# 04_MOSFET.net
KiCad netlist of a schematic drawn in Altium Designer
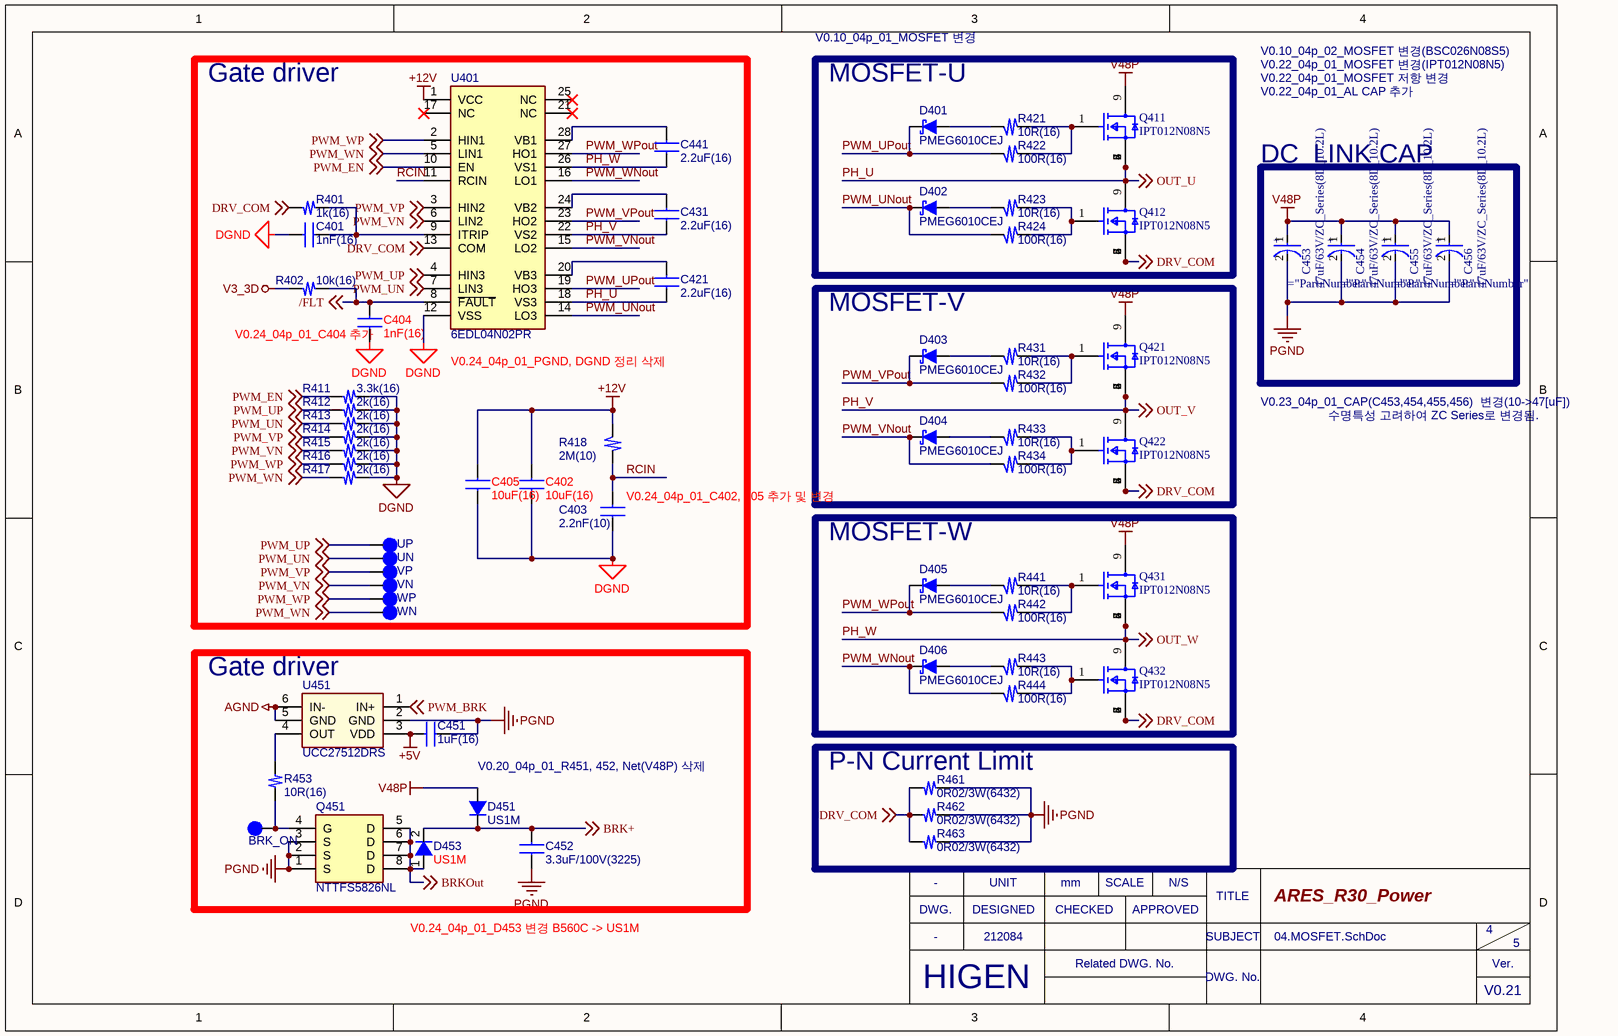
[diagram p0: 04.MOSFET.SchDoc]

(export (version "E")
  (design (tool "Eeschema 10.0.6"))
  (components
    (comp (ref "BRK_ON")
      (value "TP")
      (footprint "TP-SMD")
      (fields (field (name "MFR") "Keystone Electronics") (field (name "TIINTPARTNUMBER") "2H0026"))
      (libsource (lib "*") (part "2H_TestPointThroughHole"))
    )
    (comp (ref "C401")
      (value "1nF(16)")
      (footprint "C-1608S")
      (libsource (lib "AM437X_MAIN_LOW") (part "Cap_NP"))
    )
    (comp (ref "C402") (value "10uF(16)") (footprint "C-1608S") (libsource (lib "HIGEN") (part "Cap_NP")))
    (comp (ref "C403") (value "2.2nF(10)") (footprint "C-1005S") (libsource (lib "HIGEN") (part "Cap_NP")))
    (comp (ref "C404")
      (value "1nF(16)")
      (footprint "C-1608S")
      (libsource (lib "AM437X_MAIN_LOW") (part "Cap_NP"))
    )
    (comp (ref "C405") (value "10uF(16)") (footprint "C-1608S") (libsource (lib "HIGEN") (part "Cap_NP")))
    (comp (ref "C421") (value "2.2uF(16)") (footprint "C-1608S") (libsource (lib "HIGEN") (part "Cap_NP")))
    (comp (ref "C431") (value "2.2uF(16)") (footprint "C-1608S") (libsource (lib "HIGEN") (part "Cap_NP")))
    (comp (ref "C441") (value "2.2uF(16)") (footprint "C-1608S") (libsource (lib "HIGEN") (part "Cap_NP")))
    (comp (ref "C451")
      (value "1uF(16)")
      (footprint "C-1608S")
      (libsource (lib "AM437X_MAIN_LOW") (part "Cap_NP"))
    )
    (comp (ref "C452")
      (value "3.3uF/100V(3225)")
      (footprint "C-3225")
      (libsource (lib "HIGEN") (part "Cap_NP"))
    )
    (comp (ref "C453")
      (value "47uF/63V/ZC_Series(8D_10.2L)")
      (footprint "EC-H10")
      (description "EEE-FK1J680UP")
      (libsource (lib "ARES_R30_Power_r1") (part "EEE-FK1J680UP"))
    )
    (comp (ref "C454")
      (value "47uF/63V/ZC_Series(8D_10.2L)")
      (footprint "EC-H10")
      (description "EEE-FK1J680UP")
      (libsource (lib "ARES_R30_Power_r1") (part "EEE-FK1J680UP"))
    )
    (comp (ref "C455")
      (value "47uF/63V/ZC_Series(8D_10.2L)")
      (footprint "EC-H10")
      (description "EEE-FK1J680UP")
      (libsource (lib "ARES_R30_Power_r1") (part "EEE-FK1J680UP"))
    )
    (comp (ref "C456")
      (value "47uF/63V/ZC_Series(8D_10.2L)")
      (footprint "EC-H10")
      (description "EEE-FK1J680UP")
      (libsource (lib "ARES_R30_Power_r1") (part "EEE-FK1J680UP"))
    )
    (comp (ref "D401")
      (value "PMEG6010CEJ")
      (footprint "SOD-323")
      (libsource (lib "HIGEN") (part "Diode_schottky"))
    )
    (comp (ref "D402")
      (value "PMEG6010CEJ")
      (footprint "SOD-323")
      (libsource (lib "HIGEN") (part "Diode_schottky"))
    )
    (comp (ref "D403")
      (value "PMEG6010CEJ")
      (footprint "SOD-323")
      (libsource (lib "HIGEN") (part "Diode_schottky"))
    )
    (comp (ref "D404")
      (value "PMEG6010CEJ")
      (footprint "SOD-323")
      (libsource (lib "HIGEN") (part "Diode_schottky"))
    )
    (comp (ref "D405")
      (value "PMEG6010CEJ")
      (footprint "SOD-323")
      (libsource (lib "HIGEN") (part "Diode_schottky"))
    )
    (comp (ref "D406")
      (value "PMEG6010CEJ")
      (footprint "SOD-323")
      (libsource (lib "HIGEN") (part "Diode_schottky"))
    )
    (comp (ref "D451") (value "US1M") (footprint "SMA") (libsource (lib "") (part "Diode_1")))
    (comp (ref "D453") (value "US1M") (footprint "SMA") (libsource (lib "HIGEN") (part "Diode")))
    (comp (ref "Q411")
      (value "IPT012N08N5")
      (footprint "PG-HSOF-8-1")
      (description "TRANS 80V 300A 1.2MOHM TOLL")
      (fields
        (field (name "DIGIKEY PART NUMBER") "IAUT300N08S5N012ATMA2CT-ND")
        (field (name "MANUFACTURER") "Infineon")
      )
      (libsource (lib "ARES_R30_Power_r1") (part "IAUT300N08S5N012ATMA2"))
    )
    (comp (ref "Q412")
      (value "IPT012N08N5")
      (footprint "PG-HSOF-8-1")
      (description "TRANS 80V 300A 1.2MOHM TOLL")
      (fields
        (field (name "DIGIKEY PART NUMBER") "IAUT300N08S5N012ATMA2CT-ND")
        (field (name "MANUFACTURER") "Infineon")
      )
      (libsource (lib "ARES_R30_Power_r1") (part "IAUT300N08S5N012ATMA2"))
    )
    (comp (ref "Q421")
      (value "IPT012N08N5")
      (footprint "PG-HSOF-8-1")
      (description "TRANS 80V 300A 1.2MOHM TOLL")
      (fields
        (field (name "DIGIKEY PART NUMBER") "IAUT300N08S5N012ATMA2CT-ND")
        (field (name "MANUFACTURER") "Infineon")
      )
      (libsource (lib "ARES_R30_Power_r1") (part "IAUT300N08S5N012ATMA2"))
    )
    (comp (ref "Q422")
      (value "IPT012N08N5")
      (footprint "PG-HSOF-8-1")
      (description "TRANS 80V 300A 1.2MOHM TOLL")
      (fields
        (field (name "DIGIKEY PART NUMBER") "IAUT300N08S5N012ATMA2CT-ND")
        (field (name "MANUFACTURER") "Infineon")
      )
      (libsource (lib "ARES_R30_Power_r1") (part "IAUT300N08S5N012ATMA2"))
    )
    (comp (ref "Q431")
      (value "IPT012N08N5")
      (footprint "PG-HSOF-8-1")
      (description "TRANS 80V 300A 1.2MOHM TOLL")
      (fields
        (field (name "DIGIKEY PART NUMBER") "IAUT300N08S5N012ATMA2CT-ND")
        (field (name "MANUFACTURER") "Infineon")
      )
      (libsource (lib "ARES_R30_Power_r1") (part "IAUT300N08S5N012ATMA2"))
    )
    (comp (ref "Q432")
      (value "IPT012N08N5")
      (footprint "PG-HSOF-8-1")
      (description "TRANS 80V 300A 1.2MOHM TOLL")
      (fields
        (field (name "DIGIKEY PART NUMBER") "IAUT300N08S5N012ATMA2CT-ND")
        (field (name "MANUFACTURER") "Infineon")
      )
      (libsource (lib "ARES_R30_Power_r1") (part "IAUT300N08S5N012ATMA2"))
    )
    (comp (ref "Q451")
      (value "NTTFS5826NL")
      (footprint "WDFN-8")
      (libsource (lib "HIGEN") (part "NTTFS5826NL"))
    )
    (comp (ref "R401") (value "1k(16)") (footprint "R-1608S") (libsource (lib "") (part "Res_1")))
    (comp (ref "R402") (value "10k(16)") (footprint "R-1608S") (libsource (lib "") (part "Res_1")))
    (comp (ref "R411") (value "3.3k(16)") (footprint "R-1608S") (libsource (lib "") (part "Res_1")))
    (comp (ref "R412") (value "2k(16)") (footprint "R-1608S") (libsource (lib "") (part "Res_1")))
    (comp (ref "R413") (value "2k(16)") (footprint "R-1608S") (libsource (lib "") (part "Res_1")))
    (comp (ref "R414") (value "2k(16)") (footprint "R-1608S") (libsource (lib "") (part "Res_1")))
    (comp (ref "R415") (value "2k(16)") (footprint "R-1608S") (libsource (lib "") (part "Res_1")))
    (comp (ref "R416") (value "2k(16)") (footprint "R-1608S") (libsource (lib "") (part "Res_1")))
    (comp (ref "R417") (value "2k(16)") (footprint "R-1608S") (libsource (lib "") (part "Res_1")))
    (comp (ref "R418")
      (value "2M(10)")
      (footprint "RES-1005S")
      (libsource (lib "AM437X_MAIN_LOW") (part "Res"))
    )
    (comp (ref "R421") (value "10R(16)") (footprint "R-1608S") (libsource (lib "HIGEN") (part "Res")))
    (comp (ref "R422") (value "100R(16)") (footprint "R-1608S") (libsource (lib "HIGEN") (part "Res")))
    (comp (ref "R423") (value "10R(16)") (footprint "R-1608S") (libsource (lib "HIGEN") (part "Res")))
    (comp (ref "R424") (value "100R(16)") (footprint "R-1608S") (libsource (lib "HIGEN") (part "Res")))
    (comp (ref "R431") (value "10R(16)") (footprint "R-1608S") (libsource (lib "HIGEN") (part "Res")))
    (comp (ref "R432") (value "100R(16)") (footprint "R-1608S") (libsource (lib "HIGEN") (part "Res")))
    (comp (ref "R433") (value "10R(16)") (footprint "R-1608S") (libsource (lib "HIGEN") (part "Res")))
    (comp (ref "R434") (value "100R(16)") (footprint "R-1608S") (libsource (lib "HIGEN") (part "Res")))
    (comp (ref "R441") (value "10R(16)") (footprint "R-1608S") (libsource (lib "HIGEN") (part "Res")))
    (comp (ref "R442") (value "100R(16)") (footprint "R-1608S") (libsource (lib "HIGEN") (part "Res")))
    (comp (ref "R443") (value "10R(16)") (footprint "R-1608S") (libsource (lib "HIGEN") (part "Res")))
    (comp (ref "R444") (value "100R(16)") (footprint "R-1608S") (libsource (lib "HIGEN") (part "Res")))
    (comp (ref "R453") (value "10R(16)") (footprint "R-1608S") (libsource (lib "") (part "Res_1")))
    (comp (ref "R461") (value "0R02/3W(6432)") (footprint "R-6432") (libsource (lib "") (part "Res_1")))
    (comp (ref "R462") (value "0R02/3W(6432)") (footprint "R-6432") (libsource (lib "") (part "Res_1")))
    (comp (ref "R463") (value "0R02/3W(6432)") (footprint "R-6432") (libsource (lib "") (part "Res_1")))
    (comp (ref "U401")
      (value "6EDL04N02PR")
      (footprint "TSSOP-28")
      (libsource (lib "HIGEN") (part "6EDL04N02PR"))
    )
    (comp (ref "U451")
      (value "UCC27512DRS")
      (footprint "WSON-6")
      (libsource (lib "HIGEN") (part "UCC27512DRS"))
    )
    (comp (ref "UN")
      (value "TP")
      (footprint "TP-SMD")
      (fields (field (name "MFR") "Keystone Electronics") (field (name "TIINTPARTNUMBER") "2H0026"))
      (libsource (lib "*") (part "2H_TestPointThroughHole"))
    )
    (comp (ref "UP")
      (value "TP")
      (footprint "TP-SMD")
      (fields (field (name "MFR") "Keystone Electronics") (field (name "TIINTPARTNUMBER") "2H0026"))
      (libsource (lib "*") (part "2H_TestPointThroughHole"))
    )
    (comp (ref "VN")
      (value "TP")
      (footprint "TP-SMD")
      (fields (field (name "MFR") "Keystone Electronics") (field (name "TIINTPARTNUMBER") "2H0026"))
      (libsource (lib "*") (part "2H_TestPointThroughHole"))
    )
    (comp (ref "VP")
      (value "TP")
      (footprint "TP-SMD")
      (fields (field (name "MFR") "Keystone Electronics") (field (name "TIINTPARTNUMBER") "2H0026"))
      (libsource (lib "*") (part "2H_TestPointThroughHole"))
    )
    (comp (ref "WN")
      (value "TP")
      (footprint "TP-SMD")
      (fields (field (name "MFR") "Keystone Electronics") (field (name "TIINTPARTNUMBER") "2H0026"))
      (libsource (lib "*") (part "2H_TestPointThroughHole"))
    )
    (comp (ref "WP")
      (value "TP")
      (footprint "TP-SMD")
      (fields (field (name "MFR") "Keystone Electronics") (field (name "TIINTPARTNUMBER") "2H0026"))
      (libsource (lib "*") (part "2H_TestPointThroughHole"))
    )
  )
  (nets
    (net (code "1") (name "+5V") (class "Default")
      (node (ref "C451") (pin "1") (pinfunction "1_1") (pintype "passive"))
      (node (ref "U451") (pin "3") (pinfunction "VDD_3") (pintype "passive"))
    )
    (net (code "2") (name "+12V") (class "Default")
      (node (ref "C402") (pin "1") (pinfunction "1_1") (pintype "passive"))
      (node (ref "C405") (pin "1") (pinfunction "1_1") (pintype "passive"))
      (node (ref "R418") (pin "2") (pinfunction "2_2") (pintype "passive"))
      (node (ref "U401") (pin "1") (pinfunction "VCC_1") (pintype "passive"))
    )
    (net (code "3") (name "/PWM_UNout") (class "Default")
      (node (ref "D402") (pin "2") (pinfunction "K_2") (pintype "passive"))
      (node (ref "R424") (pin "2") (pinfunction "2_2") (pintype "passive"))
      (node (ref "U401") (pin "14") (pinfunction "LO3_14") (pintype "passive"))
    )
    (net (code "4") (name "/PWM_UPout") (class "Default")
      (node (ref "D401") (pin "2") (pinfunction "K_2") (pintype "passive"))
      (node (ref "R422") (pin "2") (pinfunction "2_2") (pintype "passive"))
      (node (ref "U401") (pin "19") (pinfunction "HO3_19") (pintype "passive"))
    )
    (net (code "5") (name "/PWM_VNout") (class "Default")
      (node (ref "D404") (pin "2") (pinfunction "K_2") (pintype "passive"))
      (node (ref "R434") (pin "2") (pinfunction "2_2") (pintype "passive"))
      (node (ref "U401") (pin "15") (pinfunction "LO2_15") (pintype "passive"))
    )
    (net (code "6") (name "/PWM_VPout") (class "Default")
      (node (ref "D403") (pin "2") (pinfunction "K_2") (pintype "passive"))
      (node (ref "R432") (pin "2") (pinfunction "2_2") (pintype "passive"))
      (node (ref "U401") (pin "23") (pinfunction "HO2_23") (pintype "passive"))
    )
    (net (code "7") (name "/PWM_WNout") (class "Default")
      (node (ref "D406") (pin "2") (pinfunction "K_2") (pintype "passive"))
      (node (ref "R444") (pin "2") (pinfunction "2_2") (pintype "passive"))
      (node (ref "U401") (pin "16") (pinfunction "LO1_16") (pintype "passive"))
    )
    (net (code "8") (name "/PWM_WPout") (class "Default")
      (node (ref "D405") (pin "2") (pinfunction "K_2") (pintype "passive"))
      (node (ref "R442") (pin "2") (pinfunction "2_2") (pintype "passive"))
      (node (ref "U401") (pin "27") (pinfunction "HO1_27") (pintype "passive"))
    )
    (net (code "9") (name "/RCIN") (class "Default")
      (node (ref "C403") (pin "2") (pinfunction "2_2") (pintype "passive"))
      (node (ref "R418") (pin "1") (pinfunction "1_1") (pintype "passive"))
      (node (ref "U401") (pin "11") (pinfunction "RCIN_11") (pintype "passive"))
    )
    (net (code "10") (name "AGND") (class "Default")
      (node (ref "U451") (pin "5") (pinfunction "GND_5") (pintype "passive"))
      (node (ref "U451") (pin "6") (pinfunction "IN-_6") (pintype "passive"))
    )
    (net (code "11") (name "BRK+") (class "Default")
      (node (ref "C452") (pin "2") (pinfunction "2_2") (pintype "passive"))
      (node (ref "D451") (pin "2") (pinfunction "K_2") (pintype "passive"))
      (node (ref "D453") (pin "2") (pinfunction "K_2") (pintype "passive"))
    )
    (net (code "12") (name "BRKOut") (class "Default")
      (node (ref "D453") (pin "1") (pinfunction "A_1") (pintype "passive"))
      (node (ref "Q451") (pin "5") (pinfunction "D_5") (pintype "passive"))
      (node (ref "Q451") (pin "6") (pinfunction "D_6") (pintype "passive"))
      (node (ref "Q451") (pin "7") (pinfunction "D_7") (pintype "passive"))
      (node (ref "Q451") (pin "8") (pinfunction "D_8") (pintype "passive"))
    )
    (net (code "13") (name "DGND") (class "Default")
      (node (ref "C401") (pin "1") (pinfunction "1_1") (pintype "passive"))
      (node (ref "C402") (pin "2") (pinfunction "2_2") (pintype "passive"))
      (node (ref "C403") (pin "1") (pinfunction "1_1") (pintype "passive"))
      (node (ref "C404") (pin "1") (pinfunction "1_1") (pintype "passive"))
      (node (ref "C405") (pin "2") (pinfunction "2_2") (pintype "passive"))
      (node (ref "R411") (pin "2") (pinfunction "P2_2") (pintype "passive"))
      (node (ref "R412") (pin "1") (pinfunction "P1_1") (pintype "passive"))
      (node (ref "R413") (pin "1") (pinfunction "P1_1") (pintype "passive"))
      (node (ref "R414") (pin "1") (pinfunction "P1_1") (pintype "passive"))
      (node (ref "R415") (pin "1") (pinfunction "P1_1") (pintype "passive"))
      (node (ref "R416") (pin "2") (pinfunction "P2_2") (pintype "passive"))
      (node (ref "R417") (pin "2") (pinfunction "P2_2") (pintype "passive"))
      (node (ref "U401") (pin "12") (pinfunction "VSS_12") (pintype "passive"))
    )
    (net (code "14") (name "DRV_COM") (class "Default")
      (node (ref "Q412") (pin "2") (pinfunction "Source_2") (pintype "passive"))
      (node (ref "Q412") (pin "3") (pinfunction "Source_3") (pintype "passive"))
      (node (ref "Q412") (pin "4") (pinfunction "Source_4") (pintype "passive"))
      (node (ref "Q412") (pin "5") (pinfunction "Source_5") (pintype "passive"))
      (node (ref "Q412") (pin "6") (pinfunction "Source_6") (pintype "passive"))
      (node (ref "Q412") (pin "7") (pinfunction "Source_7") (pintype "passive"))
      (node (ref "Q412") (pin "8") (pinfunction "Source_8") (pintype "passive"))
      (node (ref "Q422") (pin "2") (pinfunction "Source_2") (pintype "passive"))
      (node (ref "Q422") (pin "3") (pinfunction "Source_3") (pintype "passive"))
      (node (ref "Q422") (pin "4") (pinfunction "Source_4") (pintype "passive"))
      (node (ref "Q422") (pin "5") (pinfunction "Source_5") (pintype "passive"))
      (node (ref "Q422") (pin "6") (pinfunction "Source_6") (pintype "passive"))
      (node (ref "Q422") (pin "7") (pinfunction "Source_7") (pintype "passive"))
      (node (ref "Q422") (pin "8") (pinfunction "Source_8") (pintype "passive"))
      (node (ref "Q432") (pin "2") (pinfunction "Source_2") (pintype "passive"))
      (node (ref "Q432") (pin "3") (pinfunction "Source_3") (pintype "passive"))
      (node (ref "Q432") (pin "4") (pinfunction "Source_4") (pintype "passive"))
      (node (ref "Q432") (pin "5") (pinfunction "Source_5") (pintype "passive"))
      (node (ref "Q432") (pin "6") (pinfunction "Source_6") (pintype "passive"))
      (node (ref "Q432") (pin "7") (pinfunction "Source_7") (pintype "passive"))
      (node (ref "Q432") (pin "8") (pinfunction "Source_8") (pintype "passive"))
      (node (ref "R401") (pin "1") (pinfunction "P1_1") (pintype "passive"))
      (node (ref "R461") (pin "2") (pinfunction "P2_2") (pintype "passive"))
      (node (ref "R462") (pin "2") (pinfunction "P2_2") (pintype "passive"))
      (node (ref "R463") (pin "2") (pinfunction "P2_2") (pintype "passive"))
      (node (ref "U401") (pin "13") (pinfunction "COM_13") (pintype "passive"))
    )
    (net (code "15") (name "Net-(D401-A)") (class "Default")
      (node (ref "D401") (pin "1") (pinfunction "A_1") (pintype "passive"))
      (node (ref "R421") (pin "2") (pinfunction "2_2") (pintype "passive"))
    )
    (net (code "16") (name "Net-(D402-A)") (class "Default")
      (node (ref "D402") (pin "1") (pinfunction "A_1") (pintype "passive"))
      (node (ref "R423") (pin "2") (pinfunction "2_2") (pintype "passive"))
    )
    (net (code "17") (name "Net-(D403-A)") (class "Default")
      (node (ref "D403") (pin "1") (pinfunction "A_1") (pintype "passive"))
      (node (ref "R431") (pin "2") (pinfunction "2_2") (pintype "passive"))
    )
    (net (code "18") (name "Net-(D404-A)") (class "Default")
      (node (ref "D404") (pin "1") (pinfunction "A_1") (pintype "passive"))
      (node (ref "R433") (pin "2") (pinfunction "2_2") (pintype "passive"))
    )
    (net (code "19") (name "Net-(D405-A)") (class "Default")
      (node (ref "D405") (pin "1") (pinfunction "A_1") (pintype "passive"))
      (node (ref "R441") (pin "2") (pinfunction "2_2") (pintype "passive"))
    )
    (net (code "20") (name "Net-(D406-A)") (class "Default")
      (node (ref "D406") (pin "1") (pinfunction "A_1") (pintype "passive"))
      (node (ref "R443") (pin "2") (pinfunction "2_2") (pintype "passive"))
    )
    (net (code "21") (name "Net-(Q411-Gate)") (class "Default")
      (node (ref "Q411") (pin "1") (pinfunction "Gate_1") (pintype "passive"))
      (node (ref "R421") (pin "1") (pinfunction "1_1") (pintype "passive"))
      (node (ref "R422") (pin "1") (pinfunction "1_1") (pintype "passive"))
    )
    (net (code "22") (name "Net-(Q412-Gate)") (class "Default")
      (node (ref "Q412") (pin "1") (pinfunction "Gate_1") (pintype "passive"))
      (node (ref "R423") (pin "1") (pinfunction "1_1") (pintype "passive"))
      (node (ref "R424") (pin "1") (pinfunction "1_1") (pintype "passive"))
    )
    (net (code "23") (name "Net-(Q421-Gate)") (class "Default")
      (node (ref "Q421") (pin "1") (pinfunction "Gate_1") (pintype "passive"))
      (node (ref "R431") (pin "1") (pinfunction "1_1") (pintype "passive"))
      (node (ref "R432") (pin "1") (pinfunction "1_1") (pintype "passive"))
    )
    (net (code "24") (name "Net-(Q422-Gate)") (class "Default")
      (node (ref "Q422") (pin "1") (pinfunction "Gate_1") (pintype "passive"))
      (node (ref "R433") (pin "1") (pinfunction "1_1") (pintype "passive"))
      (node (ref "R434") (pin "1") (pinfunction "1_1") (pintype "passive"))
    )
    (net (code "25") (name "Net-(Q431-Gate)") (class "Default")
      (node (ref "Q431") (pin "1") (pinfunction "Gate_1") (pintype "passive"))
      (node (ref "R441") (pin "1") (pinfunction "1_1") (pintype "passive"))
      (node (ref "R442") (pin "1") (pinfunction "1_1") (pintype "passive"))
    )
    (net (code "26") (name "Net-(Q432-Gate)") (class "Default")
      (node (ref "Q432") (pin "1") (pinfunction "Gate_1") (pintype "passive"))
      (node (ref "R443") (pin "1") (pinfunction "1_1") (pintype "passive"))
      (node (ref "R444") (pin "1") (pinfunction "1_1") (pintype "passive"))
    )
    (net (code "27") (name "Net-(Q451-G)") (class "Default")
      (node (ref "BRK_ON") (pin "1") (pinfunction "1_1") (pintype "passive"))
      (node (ref "Q451") (pin "4") (pinfunction "G_4") (pintype "passive"))
      (node (ref "R453") (pin "1") (pinfunction "P1_1") (pintype "passive"))
    )
    (net (code "28") (name "Net-(R401-P2)") (class "Default")
      (node (ref "C401") (pin "2") (pinfunction "2_2") (pintype "passive"))
      (node (ref "R401") (pin "2") (pinfunction "P2_2") (pintype "passive"))
      (node (ref "U401") (pin "9") (pinfunction "ITRIP_9") (pintype "passive"))
    )
    (net (code "29") (name "Net-(R453-P2)") (class "Default")
      (node (ref "R453") (pin "2") (pinfunction "P2_2") (pintype "passive"))
      (node (ref "U451") (pin "4") (pinfunction "OUT_4") (pintype "passive"))
    )
    (net (code "30") (name "Net-(U401-VB1)") (class "Default")
      (node (ref "C441") (pin "2") (pinfunction "2_2") (pintype "passive"))
      (node (ref "U401") (pin "28") (pinfunction "VB1_28") (pintype "passive"))
    )
    (net (code "31") (name "Net-(U401-VB2)") (class "Default")
      (node (ref "C431") (pin "2") (pinfunction "2_2") (pintype "passive"))
      (node (ref "U401") (pin "24") (pinfunction "VB2_24") (pintype "passive"))
    )
    (net (code "32") (name "Net-(U401-VB3)") (class "Default")
      (node (ref "C421") (pin "1") (pinfunction "1_1") (pintype "passive"))
      (node (ref "U401") (pin "20") (pinfunction "VB3_20") (pintype "passive"))
    )
    (net (code "33") (name "OUT_U") (class "Default")
      (node (ref "C421") (pin "2") (pinfunction "2_2") (pintype "passive"))
      (node (ref "Q411") (pin "2") (pinfunction "Source_2") (pintype "passive"))
      (node (ref "Q411") (pin "3") (pinfunction "Source_3") (pintype "passive"))
      (node (ref "Q411") (pin "4") (pinfunction "Source_4") (pintype "passive"))
      (node (ref "Q411") (pin "5") (pinfunction "Source_5") (pintype "passive"))
      (node (ref "Q411") (pin "6") (pinfunction "Source_6") (pintype "passive"))
      (node (ref "Q411") (pin "7") (pinfunction "Source_7") (pintype "passive"))
      (node (ref "Q411") (pin "8") (pinfunction "Source_8") (pintype "passive"))
      (node (ref "Q412") (pin "9") (pinfunction "Drain_9") (pintype "passive"))
      (node (ref "U401") (pin "18") (pinfunction "VS3_18") (pintype "passive"))
    )
    (net (code "34") (name "OUT_V") (class "Default")
      (node (ref "C431") (pin "1") (pinfunction "1_1") (pintype "passive"))
      (node (ref "Q421") (pin "2") (pinfunction "Source_2") (pintype "passive"))
      (node (ref "Q421") (pin "3") (pinfunction "Source_3") (pintype "passive"))
      (node (ref "Q421") (pin "4") (pinfunction "Source_4") (pintype "passive"))
      (node (ref "Q421") (pin "5") (pinfunction "Source_5") (pintype "passive"))
      (node (ref "Q421") (pin "6") (pinfunction "Source_6") (pintype "passive"))
      (node (ref "Q421") (pin "7") (pinfunction "Source_7") (pintype "passive"))
      (node (ref "Q421") (pin "8") (pinfunction "Source_8") (pintype "passive"))
      (node (ref "Q422") (pin "9") (pinfunction "Drain_9") (pintype "passive"))
      (node (ref "U401") (pin "22") (pinfunction "VS2_22") (pintype "passive"))
    )
    (net (code "35") (name "OUT_W") (class "Default")
      (node (ref "C441") (pin "1") (pinfunction "1_1") (pintype "passive"))
      (node (ref "Q431") (pin "2") (pinfunction "Source_2") (pintype "passive"))
      (node (ref "Q431") (pin "3") (pinfunction "Source_3") (pintype "passive"))
      (node (ref "Q431") (pin "4") (pinfunction "Source_4") (pintype "passive"))
      (node (ref "Q431") (pin "5") (pinfunction "Source_5") (pintype "passive"))
      (node (ref "Q431") (pin "6") (pinfunction "Source_6") (pintype "passive"))
      (node (ref "Q431") (pin "7") (pinfunction "Source_7") (pintype "passive"))
      (node (ref "Q431") (pin "8") (pinfunction "Source_8") (pintype "passive"))
      (node (ref "Q432") (pin "9") (pinfunction "Drain_9") (pintype "passive"))
      (node (ref "U401") (pin "26") (pinfunction "VS1_26") (pintype "passive"))
    )
    (net (code "36") (name "PGND") (class "Default")
      (node (ref "C451") (pin "2") (pinfunction "2_2") (pintype "passive"))
      (node (ref "C452") (pin "1") (pinfunction "1_1") (pintype "passive"))
      (node (ref "C453") (pin "2") (pinfunction "A_2") (pintype "passive"))
      (node (ref "C454") (pin "2") (pinfunction "A_2") (pintype "passive"))
      (node (ref "C455") (pin "2") (pinfunction "A_2") (pintype "passive"))
      (node (ref "C456") (pin "2") (pinfunction "A_2") (pintype "passive"))
      (node (ref "Q451") (pin "1") (pinfunction "S_1") (pintype "passive"))
      (node (ref "Q451") (pin "2") (pinfunction "S_2") (pintype "passive"))
      (node (ref "Q451") (pin "3") (pinfunction "S_3") (pintype "passive"))
      (node (ref "R461") (pin "1") (pinfunction "P1_1") (pintype "passive"))
      (node (ref "R462") (pin "1") (pinfunction "P1_1") (pintype "passive"))
      (node (ref "R463") (pin "1") (pinfunction "P1_1") (pintype "passive"))
      (node (ref "U451") (pin "2") (pinfunction "GND_2") (pintype "passive"))
    )
    (net (code "37") (name "PWM_BRK") (class "Default")
      (node (ref "U451") (pin "1") (pinfunction "IN+_1") (pintype "passive"))
    )
    (net (code "38") (name "PWM_EN") (class "Default")
      (node (ref "R411") (pin "1") (pinfunction "P1_1") (pintype "passive"))
      (node (ref "U401") (pin "10") (pinfunction "EN_10") (pintype "passive"))
    )
    (net (code "39") (name "PWM_UN") (class "Default")
      (node (ref "R413") (pin "2") (pinfunction "P2_2") (pintype "passive"))
      (node (ref "U401") (pin "7") (pinfunction "LIN3_7") (pintype "passive"))
      (node (ref "UN") (pin "1") (pinfunction "1_1") (pintype "passive"))
    )
    (net (code "40") (name "PWM_UP") (class "Default")
      (node (ref "R412") (pin "2") (pinfunction "P2_2") (pintype "passive"))
      (node (ref "U401") (pin "4") (pinfunction "HIN3_4") (pintype "passive"))
      (node (ref "UP") (pin "1") (pinfunction "1_1") (pintype "passive"))
    )
    (net (code "41") (name "PWM_VN") (class "Default")
      (node (ref "R415") (pin "2") (pinfunction "P2_2") (pintype "passive"))
      (node (ref "U401") (pin "6") (pinfunction "LIN2_6") (pintype "passive"))
      (node (ref "VN") (pin "1") (pinfunction "1_1") (pintype "passive"))
    )
    (net (code "42") (name "PWM_VP") (class "Default")
      (node (ref "R414") (pin "2") (pinfunction "P2_2") (pintype "passive"))
      (node (ref "U401") (pin "3") (pinfunction "HIN2_3") (pintype "passive"))
      (node (ref "VP") (pin "1") (pinfunction "1_1") (pintype "passive"))
    )
    (net (code "43") (name "PWM_WN") (class "Default")
      (node (ref "R417") (pin "1") (pinfunction "P1_1") (pintype "passive"))
      (node (ref "U401") (pin "5") (pinfunction "LIN1_5") (pintype "passive"))
      (node (ref "WN") (pin "1") (pinfunction "1_1") (pintype "passive"))
    )
    (net (code "44") (name "PWM_WP") (class "Default")
      (node (ref "R416") (pin "1") (pinfunction "P1_1") (pintype "passive"))
      (node (ref "U401") (pin "2") (pinfunction "HIN1_2") (pintype "passive"))
      (node (ref "WP") (pin "1") (pinfunction "1_1") (pintype "passive"))
    )
    (net (code "45") (name "V3_3D") (class "Default")
      (node (ref "R402") (pin "1") (pinfunction "P1_1") (pintype "passive"))
    )
    (net (code "46") (name "V48P") (class "Default")
      (node (ref "C453") (pin "1") (pinfunction "C_1") (pintype "passive"))
      (node (ref "C454") (pin "1") (pinfunction "C_1") (pintype "passive"))
      (node (ref "C455") (pin "1") (pinfunction "C_1") (pintype "passive"))
      (node (ref "C456") (pin "1") (pinfunction "C_1") (pintype "passive"))
      (node (ref "D451") (pin "1") (pinfunction "A_1") (pintype "passive"))
      (node (ref "Q411") (pin "9") (pinfunction "Drain_9") (pintype "passive"))
      (node (ref "Q421") (pin "9") (pinfunction "Drain_9") (pintype "passive"))
      (node (ref "Q431") (pin "9") (pinfunction "Drain_9") (pintype "passive"))
    )
    (net (code "47") (name "unconnected-(U401-NC-Pad17)") (class "Default")
      (node (ref "U401") (pin "17") (pinfunction "NC_17") (pintype "passive+no_connect"))
    )
    (net (code "48") (name "unconnected-(U401-NC-Pad21)") (class "Default")
      (node (ref "U401") (pin "21") (pinfunction "NC_21") (pintype "passive+no_connect"))
    )
    (net (code "49") (name "unconnected-(U401-NC-Pad25)") (class "Default")
      (node (ref "U401") (pin "25") (pinfunction "NC_25") (pintype "passive+no_connect"))
    )
    (net (code "50") (name "{slash}FLT") (class "Default")
      (node (ref "C404") (pin "2") (pinfunction "2_2") (pintype "passive"))
      (node (ref "R402") (pin "2") (pinfunction "P2_2") (pintype "passive"))
      (node (ref "U401") (pin "8") (pinfunction "~{FAULT}_8") (pintype "passive"))
    )
  )
)
